# PLD_Top.net
KiCad netlist of a schematic drawn in Altium Designer
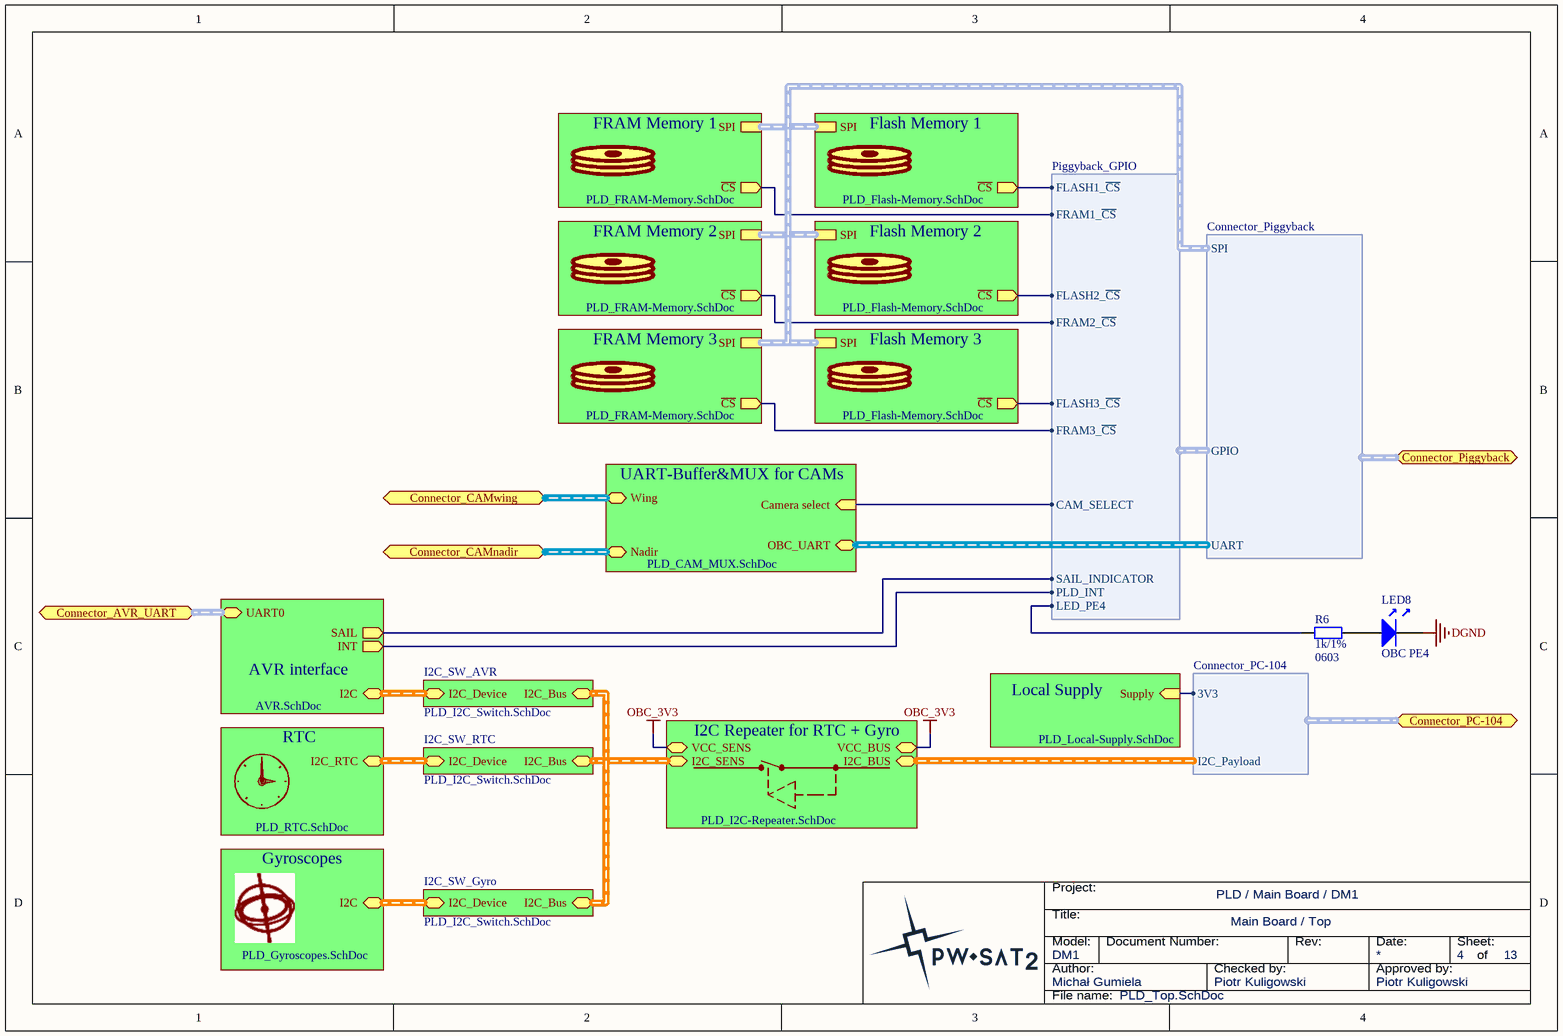
[diagram p0: PLD_Top.SchDoc]

(export (version "E")
  (design (tool "Eeschema 10.0.6"))
  (components
    (comp (ref "LED8")
      (value "OBC PE4")
      (footprint "SMD_LED_1206")
      (description "LED diode, SMD1206 package.")
      (libsource (lib "diodes") (part "LED-1206_RED"))
    )
    (comp (ref "R6")
      (value "1k/1%")
      (footprint "SMD_Resistor_0603")
      (description "1k/1% Vishay CRCW 0603 Resistor. 100mW, 100ppm, 75V.")
      (fields
        (field (name "MANUFACTURER") "Vishay")
        (field (name "MANUFACTURERPARTNUMBER") "CRCW06031K00FKxxxx")
        (field (name "PACKAGE") "0603")
      )
      (libsource (lib "resistors") (part "CRCW06031K00FKxxxx"))
    )
  )
  (nets
    (net (code "23") (name "/LED_PE4") (class "Default")
      (node (ref "R6") (pin "1") (pinfunction "1_1") (pintype "passive"))
    )
    (net (code "31") (name "DGND") (class "Default")
      (node (ref "LED8") (pin "K") (pinfunction "K_K") (pintype "passive"))
    )
    (net (code "32") (name "Net-(LED8-PadA)") (class "Default")
      (node (ref "LED8") (pin "A") (pinfunction "A_A") (pintype "passive"))
      (node (ref "R6") (pin "2") (pinfunction "2_2") (pintype "passive"))
    )
  )
)
